# H1FR7x_Frontend_1.net
KiCad netlist of a schematic drawn in Altium Designer
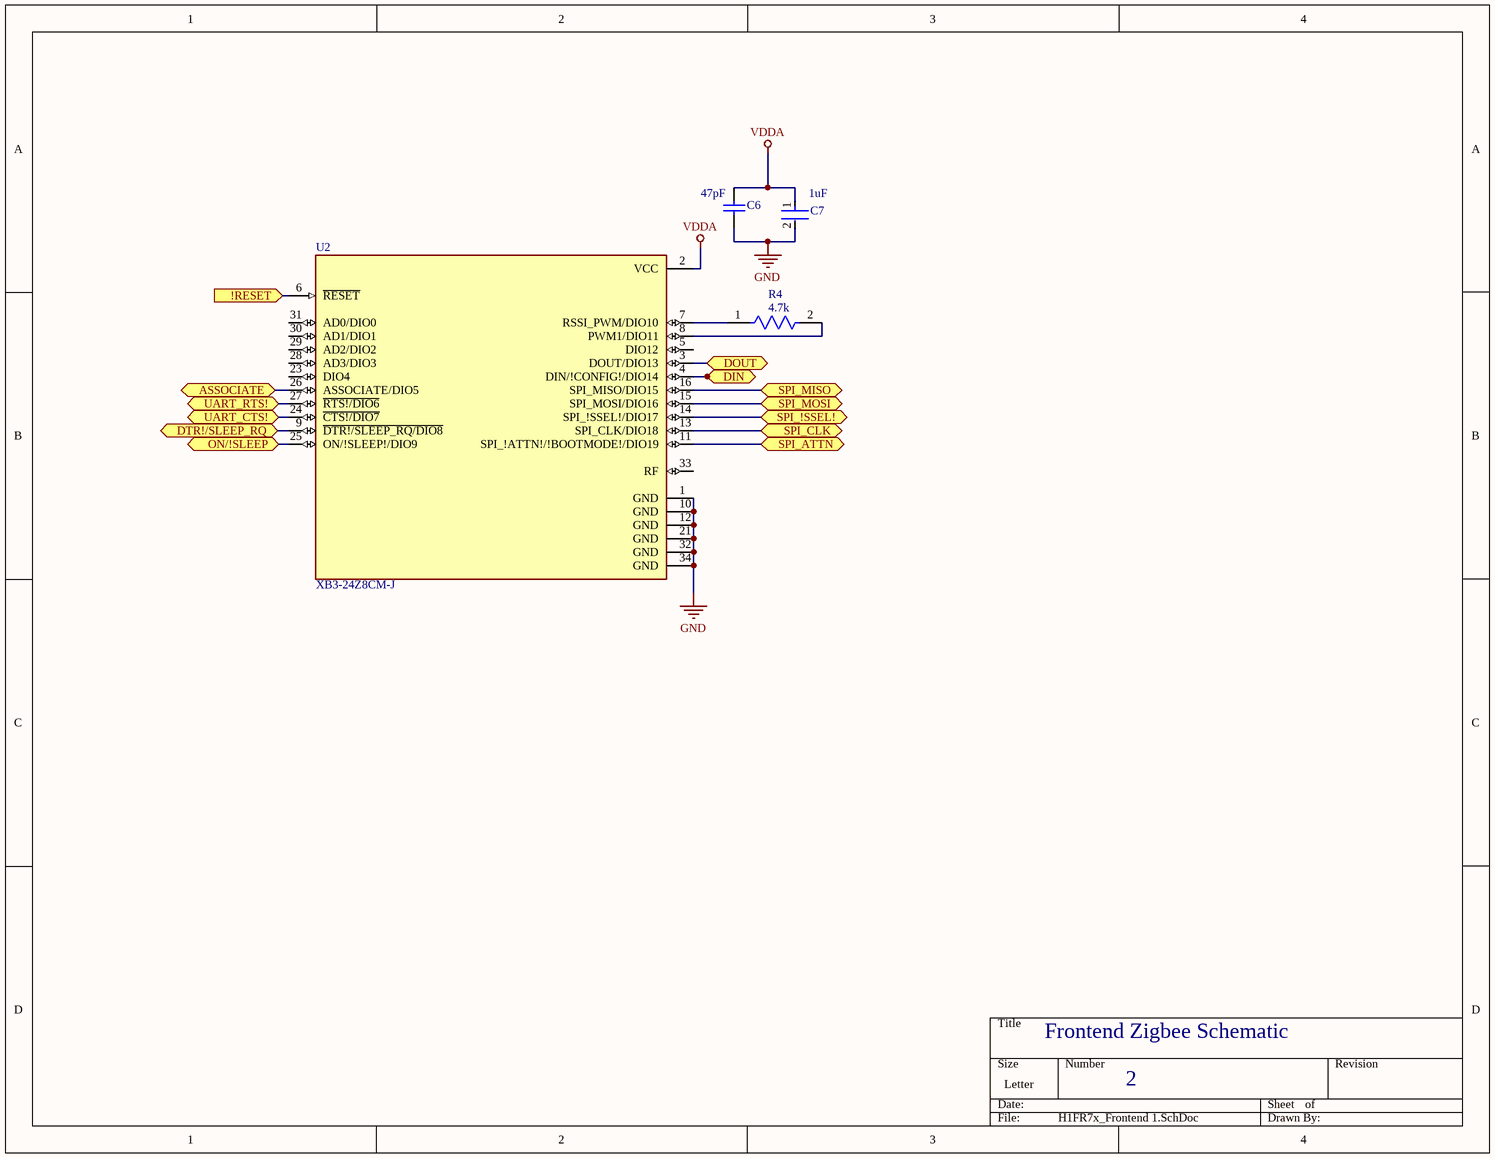
[diagram p0: H1FR7x_Frontend 1.SchDoc]

(export (version "E")
  (design (tool "Eeschema 10.0.6"))
  (components
    (comp (ref "C6")
      (value "47pF")
      (footprint "CAPC1608X90X35NL15T15")
      (fields
        (field (name "PART NUMBER") "06035A470GAT2A")
        (field (name "MANUFACTURER") "AVX Interconnect / Elco")
      )
      (libsource (lib "Altium Content Vault") (part "CAP"))
    )
    (comp (ref "C7")
      (value "C0603X105J9RACAUTO")
      (footprint "FP-C0603X105J9RACAUTO-MFG")
      (description "CAP CER 1UF 6.3V X7R 0603")
      (fields (field (name "CAPACITANCE") "1uF") (field (name "TOLERANCE") "5%"))
      (libsource (lib "Altium Content Vault") (part "02cd4be3c70576c341d710602a673aa"))
    )
    (comp (ref "R4")
      (value "4.7k")
      (footprint "FP-TFCR0603-IPC_B")
      (description "RES Thin Film,  4.7kΩ, 1%, 0.1W, 50ppm/°C, 0603")
      (fields (field (name "Comment") "TFCR0603-10W-C-4701FT"))
      (libsource (lib "Altium Content Vault") (part "1029c3af85768c4190bb7ad29bc67b5"))
    )
    (comp (ref "U2")
      (value "XB3-24Z8CM-J")
      (footprint "XCVR_XB3-24Z8CM-J")
      (description "802.15.4 ZigbeeÂ® Transceiver Module 2.4GHz Integrated, Chip Surface Mount")
      (fields (field (name "MF") "Digi International"))
      (libsource (lib "XB3-24Z8CM-J") (part "XB3-24Z8CM-J"))
    )
  )
  (nets
    (net (code "1") (name "/!RESET") (class "Default")
      (node (ref "U2") (pin "6") (pinfunction "~{RESET}_6") (pintype "input"))
    )
    (net (code "2") (name "/ASSOCIATE") (class "Default")
      (node (ref "U2") (pin "26") (pinfunction "ASSOCIATE/DIO5_26") (pintype "bidirectional"))
    )
    (net (code "3") (name "/DIN") (class "Default")
      (node (ref "U2") (pin "4") (pinfunction "DIN/!CONFIG!/DIO14_4") (pintype "bidirectional"))
    )
    (net (code "4") (name "/DOUT") (class "Default")
      (node (ref "U2") (pin "3") (pinfunction "DOUT/DIO13_3") (pintype "bidirectional"))
    )
    (net (code "5") (name "/DTR!{slash}SLEEP_RQ") (class "Default")
      (node (ref "U2") (pin "9") (pinfunction "~{DTR!/SLEEP_RQ/DIO8}_9") (pintype "bidirectional"))
    )
    (net (code "6") (name "/ON{slash}!SLEEP") (class "Default")
      (node (ref "U2") (pin "25") (pinfunction "ON/!SLEEP!/DIO9_25") (pintype "bidirectional"))
    )
    (net (code "7") (name "/SPI_!SSEL!") (class "Default")
      (node (ref "U2") (pin "14") (pinfunction "SPI_!SSEL!/DIO17_14") (pintype "bidirectional"))
    )
    (net (code "8") (name "/SPI_ATTN") (class "Default")
      (node (ref "U2") (pin "11") (pinfunction "SPI_!ATTN!/!BOOTMODE!/DIO19_11") (pintype "bidirectional"))
    )
    (net (code "9") (name "/SPI_CLK") (class "Default")
      (node (ref "U2") (pin "13") (pinfunction "SPI_CLK/DIO18_13") (pintype "bidirectional"))
    )
    (net (code "10") (name "/SPI_MISO") (class "Default")
      (node (ref "U2") (pin "16") (pinfunction "SPI_MISO/DIO15_16") (pintype "bidirectional"))
    )
    (net (code "11") (name "/SPI_MOSI") (class "Default")
      (node (ref "U2") (pin "15") (pinfunction "SPI_MOSI/DIO16_15") (pintype "bidirectional"))
    )
    (net (code "12") (name "/UART_CTS!") (class "Default")
      (node (ref "U2") (pin "24") (pinfunction "~{CTS!/DIO7}_24") (pintype "bidirectional"))
    )
    (net (code "13") (name "/UART_RTS!") (class "Default")
      (node (ref "U2") (pin "27") (pinfunction "~{RTS!/DIO6}_27") (pintype "bidirectional"))
    )
    (net (code "14") (name "GND") (class "Default")
      (node (ref "C6") (pin "1") (pinfunction "1_1") (pintype "passive"))
      (node (ref "C7") (pin "2") (pinfunction "2_2") (pintype "passive"))
      (node (ref "U2") (pin "1") (pinfunction "GND_1") (pintype "power_in"))
      (node (ref "U2") (pin "10") (pinfunction "GND_10") (pintype "power_in"))
      (node (ref "U2") (pin "12") (pinfunction "GND_12") (pintype "power_in"))
      (node (ref "U2") (pin "21") (pinfunction "GND_21") (pintype "power_in"))
      (node (ref "U2") (pin "32") (pinfunction "GND_32") (pintype "power_in"))
      (node (ref "U2") (pin "34") (pinfunction "GND_34") (pintype "power_in"))
    )
    (net (code "15") (name "Net-(U2-PWM1{slash}DIO11)") (class "Default")
      (node (ref "R4") (pin "2") (pinfunction "2_2") (pintype "passive"))
      (node (ref "U2") (pin "8") (pinfunction "PWM1/DIO11_8") (pintype "bidirectional"))
    )
    (net (code "16") (name "Net-(U2-RSSI_PWM{slash}DIO10)") (class "Default")
      (node (ref "R4") (pin "1") (pinfunction "1_1") (pintype "passive"))
      (node (ref "U2") (pin "7") (pinfunction "RSSI_PWM/DIO10_7") (pintype "bidirectional"))
    )
    (net (code "17") (name "VDDA") (class "Default")
      (node (ref "C6") (pin "2") (pinfunction "2_2") (pintype "passive"))
      (node (ref "C7") (pin "1") (pinfunction "1_1") (pintype "passive"))
      (node (ref "U2") (pin "2") (pinfunction "VCC_2") (pintype "power_in"))
    )
    (net (code "18") (name "unconnected-(U2-AD0{slash}DIO0-Pad31)") (class "Default")
      (node (ref "U2") (pin "31") (pinfunction "AD0/DIO0_31") (pintype "bidirectional"))
    )
    (net (code "19") (name "unconnected-(U2-AD1{slash}DIO1-Pad30)") (class "Default")
      (node (ref "U2") (pin "30") (pinfunction "AD1/DIO1_30") (pintype "bidirectional"))
    )
    (net (code "20") (name "unconnected-(U2-AD2{slash}DIO2-Pad29)") (class "Default")
      (node (ref "U2") (pin "29") (pinfunction "AD2/DIO2_29") (pintype "bidirectional"))
    )
    (net (code "21") (name "unconnected-(U2-AD3{slash}DIO3-Pad28)") (class "Default")
      (node (ref "U2") (pin "28") (pinfunction "AD3/DIO3_28") (pintype "bidirectional"))
    )
    (net (code "22") (name "unconnected-(U2-DIO4-Pad23)") (class "Default")
      (node (ref "U2") (pin "23") (pinfunction "DIO4_23") (pintype "bidirectional"))
    )
    (net (code "23") (name "unconnected-(U2-DIO12-Pad5)") (class "Default")
      (node (ref "U2") (pin "5") (pinfunction "DIO12_5") (pintype "bidirectional"))
    )
    (net (code "24") (name "unconnected-(U2-RF-Pad33)") (class "Default")
      (node (ref "U2") (pin "33") (pinfunction "RF_33") (pintype "bidirectional"))
    )
  )
)
